# sensor-1.net
KiCad netlist of a schematic drawn in Altium Designer
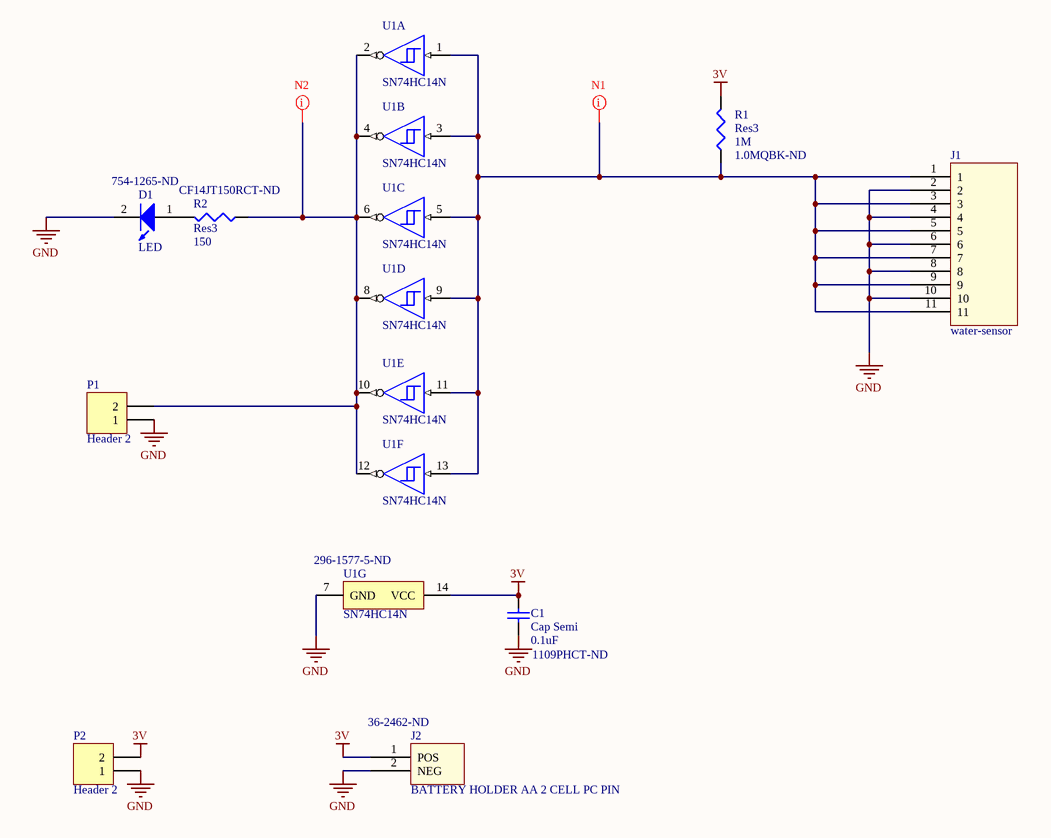
[diagram p0: sensor-1.SchDoc]

(export (version "E")
  (design (tool "Eeschema 10.0.6"))
  (components
    (comp (ref "C1")
      (value "Cap Semi")
      (footprint "A104K15X7RF5TAA")
      (description "Capacitor (Semiconductor SIM Model)")
      (fields
        (field (name "ALTIUM_VALUE") "0.1uF")
        (field (name "SUPPLIER PART NUMBER 1") "1109PHCT-ND")
        (field (name "MANUFACTURER") "Vishay BCcomponents")
        (field (name "MANUFACTURER PART NUMBER") "A104K15X7RF5TAA")
        (field (name "PUBLISHER") "Altium Limited")
      )
      (libsource (lib "Miscellaneous Devices") (part "Cap Semi"))
    )
    (comp (ref "D1")
      (value "LED")
      (footprint "WP7113LGD")
      (fields
        (field (name "SUPPLIER PART NUMBER 1") "754-1265-ND")
        (field (name "MANUFACTURER") "Kingbright")
        (field (name "MANUFACTURER PART NUMBER") "WP7113LGD")
      )
      (libsource (lib "Kingbright") (part "LED"))
    )
    (comp (ref "J1")
      (value "water-sensor")
      (footprint "water-sensor")
      (description "Water sensor footprint")
      (libsource (lib "water-sensor-footprint") (part "Water-sensor"))
    )
    (comp (ref "J2")
      (value "BATTERY HOLDER AA 2 CELL PC PIN")
      (footprint "2462")
      (description "Battery Holder (Open) AA 2 Cell PC Pin")
      (fields
        (field (name "SUPPLIER PART NUMBER 1") "36-2462-ND")
        (field (name "MANUFACTURER") "Keystone Electronics")
        (field (name "MANUFACTURER PART NUMBER") "2462")
      )
      (libsource (lib "keystone") (part "2462"))
    )
    (comp (ref "P1")
      (value "Header 2")
      (footprint "HDR1X2")
      (description "Header, 2-Pin")
      (fields (field (name "PUBLISHER") "Altium Limited"))
      (libsource (lib "Miscellaneous Connectors") (part "Header 2"))
    )
    (comp (ref "P2")
      (value "Header 2")
      (footprint "HDR1X2")
      (description "Header, 2-Pin")
      (fields (field (name "PUBLISHER") "Altium Limited"))
      (libsource (lib "Miscellaneous Connectors") (part "Header 2"))
    )
    (comp (ref "R1")
      (value "Res3")
      (footprint "CFR-25JB-52-1M")
      (description "Resistor")
      (fields
        (field (name "ALTIUM_VALUE") "1M")
        (field (name "SUPPLIER PART NUMBER 1") "1.0MQBK-ND")
        (field (name "MANUFACTURER") "Yageo")
        (field (name "MANUFACTURER PART NUMBER") "CFR-25JB-52-1M")
        (field (name "PUBLISHER") "Altium Limited")
      )
      (libsource (lib "Miscellaneous Devices") (part "Res3"))
    )
    (comp (ref "R2")
      (value "Res3")
      (footprint "CF14JT150R")
      (description "Resistor")
      (fields
        (field (name "ALTIUM_VALUE") "150")
        (field (name "SUPPLIER PART NUMBER 1") "CF14JT150RCT-ND")
        (field (name "MANUFACTURER") "Stackpole Electronics")
        (field (name "MANUFACTURER PART NUMBER") "CF14JT150R")
        (field (name "PUBLISHER") "Altium Limited")
      )
      (libsource (lib "Miscellaneous Devices") (part "Res3"))
    )
    (comp (ref "U1")
      (value "SN74HC14N")
      (footprint "N0014A")
      (description "Hex Schmitt-Trigger Inverters, N0014A, TUBE")
      (fields
        (field (name "MANUFACTURER") "Texas Instruments")
        (field (name "GENERIC PART NUMBER") "SN74HC14")
        (field (name "SUPPLIER PART NUMBER 1") "296-1577-5-ND")
      )
      (libsource (lib "Altium Content Vault") (part "TI-CD_SNX4XXXXXX4X_19A-14-SCHMITT"))
    )
  )
  (nets
    (net (code "1") (name "3V") (class "Default")
      (node (ref "C1") (pin "2") (pinfunction "2_2") (pintype "passive"))
      (node (ref "J2") (pin "1") (pinfunction "POS_1") (pintype "power_in"))
      (node (ref "P2") (pin "2") (pinfunction "2_2") (pintype "passive"))
      (node (ref "R1") (pin "2") (pinfunction "2_2") (pintype "passive"))
      (node (ref "U1") (pin "14") (pinfunction "VCC_14") (pintype "power_in"))
    )
    (net (code "2") (name "GND") (class "Default")
      (node (ref "C1") (pin "1") (pinfunction "1_1") (pintype "passive"))
      (node (ref "D1") (pin "2") (pinfunction "K_2") (pintype "passive"))
      (node (ref "J1") (pin "10") (pinfunction "10_10") (pintype "passive"))
      (node (ref "J1") (pin "2") (pinfunction "2_2") (pintype "passive"))
      (node (ref "J1") (pin "4") (pinfunction "4_4") (pintype "passive"))
      (node (ref "J1") (pin "6") (pinfunction "6_6") (pintype "passive"))
      (node (ref "J1") (pin "8") (pinfunction "8_8") (pintype "passive"))
      (node (ref "J2") (pin "2") (pinfunction "NEG_2") (pintype "power_in"))
      (node (ref "P1") (pin "1") (pinfunction "1_1") (pintype "passive"))
      (node (ref "P2") (pin "1") (pinfunction "1_1") (pintype "passive"))
      (node (ref "U1") (pin "7") (pinfunction "GND_7") (pintype "power_in"))
    )
    (net (code "3") (name "Net-(D1-A)") (class "Default")
      (node (ref "D1") (pin "1") (pinfunction "A_1") (pintype "passive"))
      (node (ref "R2") (pin "2") (pinfunction "2_2") (pintype "passive"))
    )
    (net (code "4") (name "Net-(U1A-1A)") (class "Default")
      (node (ref "J1") (pin "1") (pinfunction "1_1") (pintype "passive"))
      (node (ref "J1") (pin "11") (pinfunction "11_11") (pintype "passive"))
      (node (ref "J1") (pin "3") (pinfunction "3_3") (pintype "passive"))
      (node (ref "J1") (pin "5") (pinfunction "5_5") (pintype "passive"))
      (node (ref "J1") (pin "7") (pinfunction "7_7") (pintype "passive"))
      (node (ref "J1") (pin "9") (pinfunction "9_9") (pintype "passive"))
      (node (ref "R1") (pin "1") (pinfunction "1_1") (pintype "passive"))
      (node (ref "U1") (pin "1") (pinfunction "1A_1") (pintype "input"))
      (node (ref "U1") (pin "11") (pinfunction "5A_11") (pintype "input"))
      (node (ref "U1") (pin "13") (pinfunction "6A_13") (pintype "input"))
      (node (ref "U1") (pin "3") (pinfunction "2A_3") (pintype "input"))
      (node (ref "U1") (pin "5") (pinfunction "3A_5") (pintype "input"))
      (node (ref "U1") (pin "9") (pinfunction "4A_9") (pintype "input"))
    )
    (net (code "5") (name "Net-(U1A-~{1Y})") (class "Default")
      (node (ref "P1") (pin "2") (pinfunction "2_2") (pintype "passive"))
      (node (ref "R2") (pin "1") (pinfunction "1_1") (pintype "passive"))
      (node (ref "U1") (pin "10") (pinfunction "~{5Y}_10") (pintype "output"))
      (node (ref "U1") (pin "12") (pinfunction "~{6Y}_12") (pintype "output"))
      (node (ref "U1") (pin "2") (pinfunction "~{1Y}_2") (pintype "output"))
      (node (ref "U1") (pin "4") (pinfunction "~{2Y}_4") (pintype "output"))
      (node (ref "U1") (pin "6") (pinfunction "~{3Y}_6") (pintype "output"))
      (node (ref "U1") (pin "8") (pinfunction "~{4Y}_8") (pintype "output"))
    )
  )
)
